# femtoduino_motor_shield.net
KiCad netlist of a schematic drawn in EAGLE
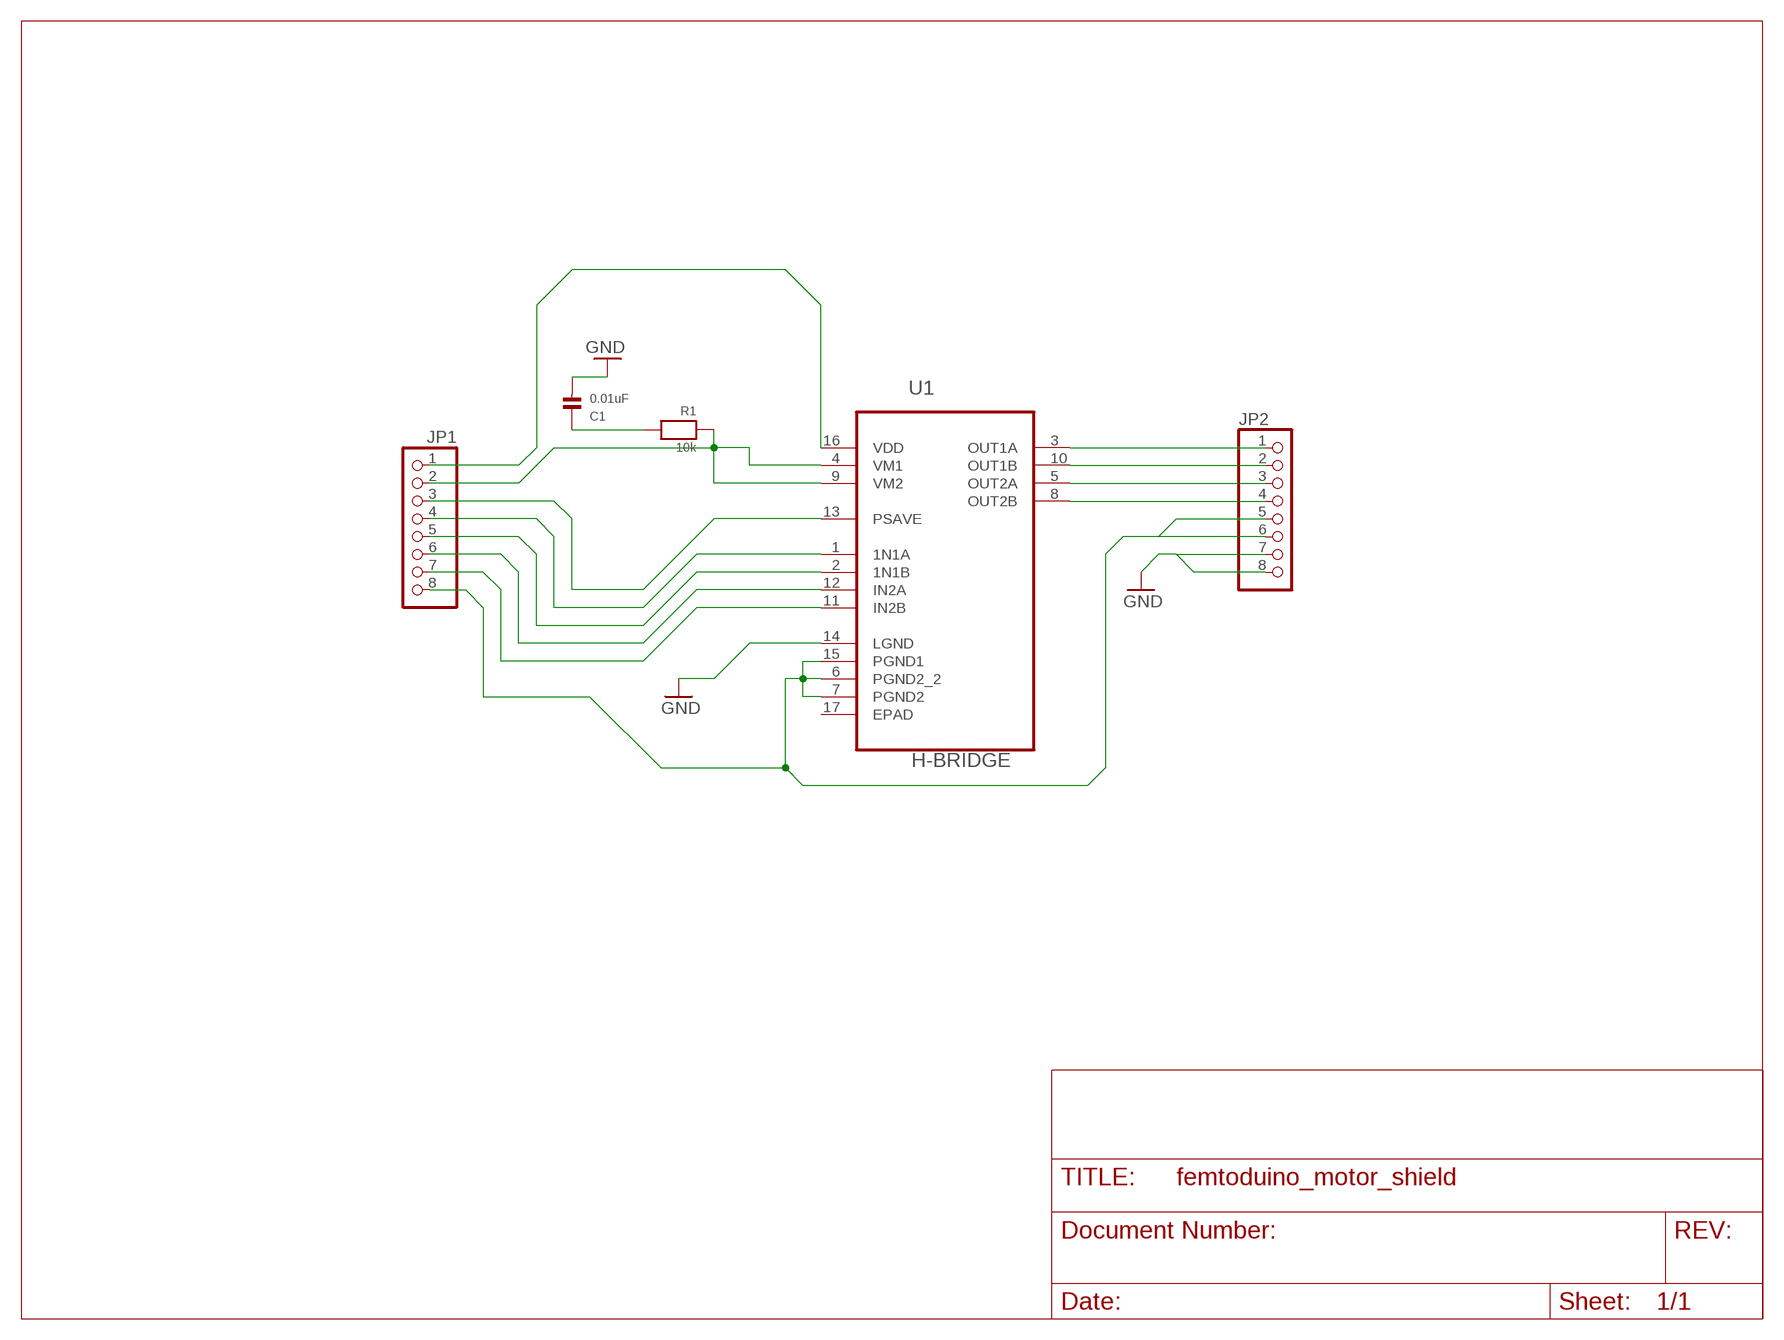
[diagram p0: schematic, sheet 1]

(export (version "E")
  (design (tool "Eeschema 10.0.6"))
  (components
    (comp (ref "C1")
      (value "0.01uF")
      (footprint "eagle-import:0603")
      (libsource (lib "eagle-import") (part "CAP_CERAMIC0603"))
    )
    (comp (ref "JP1")
      (value "PINHD-1X8")
      (footprint "eagle-import:1X08")
      (libsource (lib "eagle-import") (part "PINHD-1X8"))
    )
    (comp (ref "JP2")
      (value "PINHD-1X8")
      (footprint "eagle-import:1X08")
      (libsource (lib "eagle-import") (part "PINHD-1X8"))
    )
    (comp (ref "R1")
      (value "10k")
      (footprint "eagle-import:0603")
      (libsource (lib "eagle-import") (part "RESISTOR0603"))
    )
    (comp (ref "U1")
      (value "H-BRIDGE")
      (footprint "eagle-import:QFN50P300X300X100-17N")
      (fields (field (name "MPN") "MPC17C724EP"))
      (libsource (lib "eagle-import") (part "MPC17C724EP"))
    )
  )
  (nets
    (net (code "1") (name "GND") (class "Default")
      (node (ref "C1") (pin "1") (pinfunction "P$1_1") (pintype "passive"))
      (node (ref "C1") (pin "2") (pinfunction "P$2_2") (pintype "passive"))
      (node (ref "JP2") (pin "7") (pinfunction "7_7") (pintype "passive"))
      (node (ref "JP2") (pin "8") (pinfunction "8_8") (pintype "passive"))
      (node (ref "R1") (pin "2") (pinfunction "2_2") (pintype "passive"))
      (node (ref "U1") (pin "14") (pinfunction "LGND_14") (pintype "passive"))
    )
    (net (code "2") (name "Net-(U1-1N1A)") (class "Default")
      (node (ref "JP1") (pin "4") (pinfunction "4_4") (pintype "passive"))
      (node (ref "U1") (pin "1") (pinfunction "1N1A_1") (pintype "input"))
    )
    (net (code "3") (name "Net-(U1-1N1B)") (class "Default")
      (node (ref "JP1") (pin "5") (pinfunction "5_5") (pintype "passive"))
      (node (ref "U1") (pin "2") (pinfunction "1N1B_2") (pintype "input"))
    )
    (net (code "4") (name "Net-(U1-IN2A)") (class "Default")
      (node (ref "JP1") (pin "6") (pinfunction "6_6") (pintype "passive"))
      (node (ref "U1") (pin "12") (pinfunction "IN2A_12") (pintype "input"))
    )
    (net (code "5") (name "Net-(U1-IN2B)") (class "Default")
      (node (ref "JP1") (pin "7") (pinfunction "7_7") (pintype "passive"))
      (node (ref "U1") (pin "11") (pinfunction "IN2B_11") (pintype "input"))
    )
    (net (code "6") (name "Net-(U1-OUT1A)") (class "Default")
      (node (ref "JP2") (pin "1") (pinfunction "1_1") (pintype "passive"))
      (node (ref "U1") (pin "3") (pinfunction "OUT1A_3") (pintype "output"))
    )
    (net (code "7") (name "Net-(U1-OUT1B)") (class "Default")
      (node (ref "JP2") (pin "2") (pinfunction "2_2") (pintype "passive"))
      (node (ref "U1") (pin "10") (pinfunction "OUT1B_10") (pintype "output"))
    )
    (net (code "8") (name "Net-(U1-OUT2A)") (class "Default")
      (node (ref "JP2") (pin "3") (pinfunction "3_3") (pintype "passive"))
      (node (ref "U1") (pin "5") (pinfunction "OUT2A_5") (pintype "output"))
    )
    (net (code "9") (name "Net-(U1-OUT2B)") (class "Default")
      (node (ref "JP2") (pin "4") (pinfunction "4_4") (pintype "passive"))
      (node (ref "U1") (pin "8") (pinfunction "OUT2B_8") (pintype "output"))
    )
    (net (code "10") (name "Net-(U1-PGND1)") (class "Default")
      (node (ref "JP1") (pin "8") (pinfunction "8_8") (pintype "passive"))
      (node (ref "JP2") (pin "5") (pinfunction "5_5") (pintype "passive"))
      (node (ref "JP2") (pin "6") (pinfunction "6_6") (pintype "passive"))
      (node (ref "U1") (pin "15") (pinfunction "PGND1_15") (pintype "passive"))
      (node (ref "U1") (pin "6") (pinfunction "PGND2_2_6") (pintype "passive"))
      (node (ref "U1") (pin "7") (pinfunction "PGND2_7") (pintype "passive"))
    )
    (net (code "11") (name "Net-(U1-PSAVE)") (class "Default")
      (node (ref "JP1") (pin "3") (pinfunction "3_3") (pintype "passive"))
      (node (ref "U1") (pin "13") (pinfunction "PSAVE_13") (pintype "input"))
    )
    (net (code "12") (name "Net-(U1-VDD)") (class "Default")
      (node (ref "JP1") (pin "1") (pinfunction "1_1") (pintype "passive"))
      (node (ref "U1") (pin "16") (pinfunction "VDD_16") (pintype "power_in"))
    )
    (net (code "13") (name "Net-(U1-VM1)") (class "Default")
      (node (ref "JP1") (pin "2") (pinfunction "2_2") (pintype "passive"))
      (node (ref "R1") (pin "1") (pinfunction "1_1") (pintype "passive"))
      (node (ref "U1") (pin "4") (pinfunction "VM1_4") (pintype "power_in"))
      (node (ref "U1") (pin "9") (pinfunction "VM2_9") (pintype "power_in"))
    )
    (net (code "14") (name "unconnected-(U1-EPAD-Pad17)") (class "Default")
      (node (ref "U1") (pin "17") (pinfunction "EPAD_17") (pintype "passive"))
    )
  )
)
